# Battery.net
KiCad netlist of a schematic drawn in Altium Designer
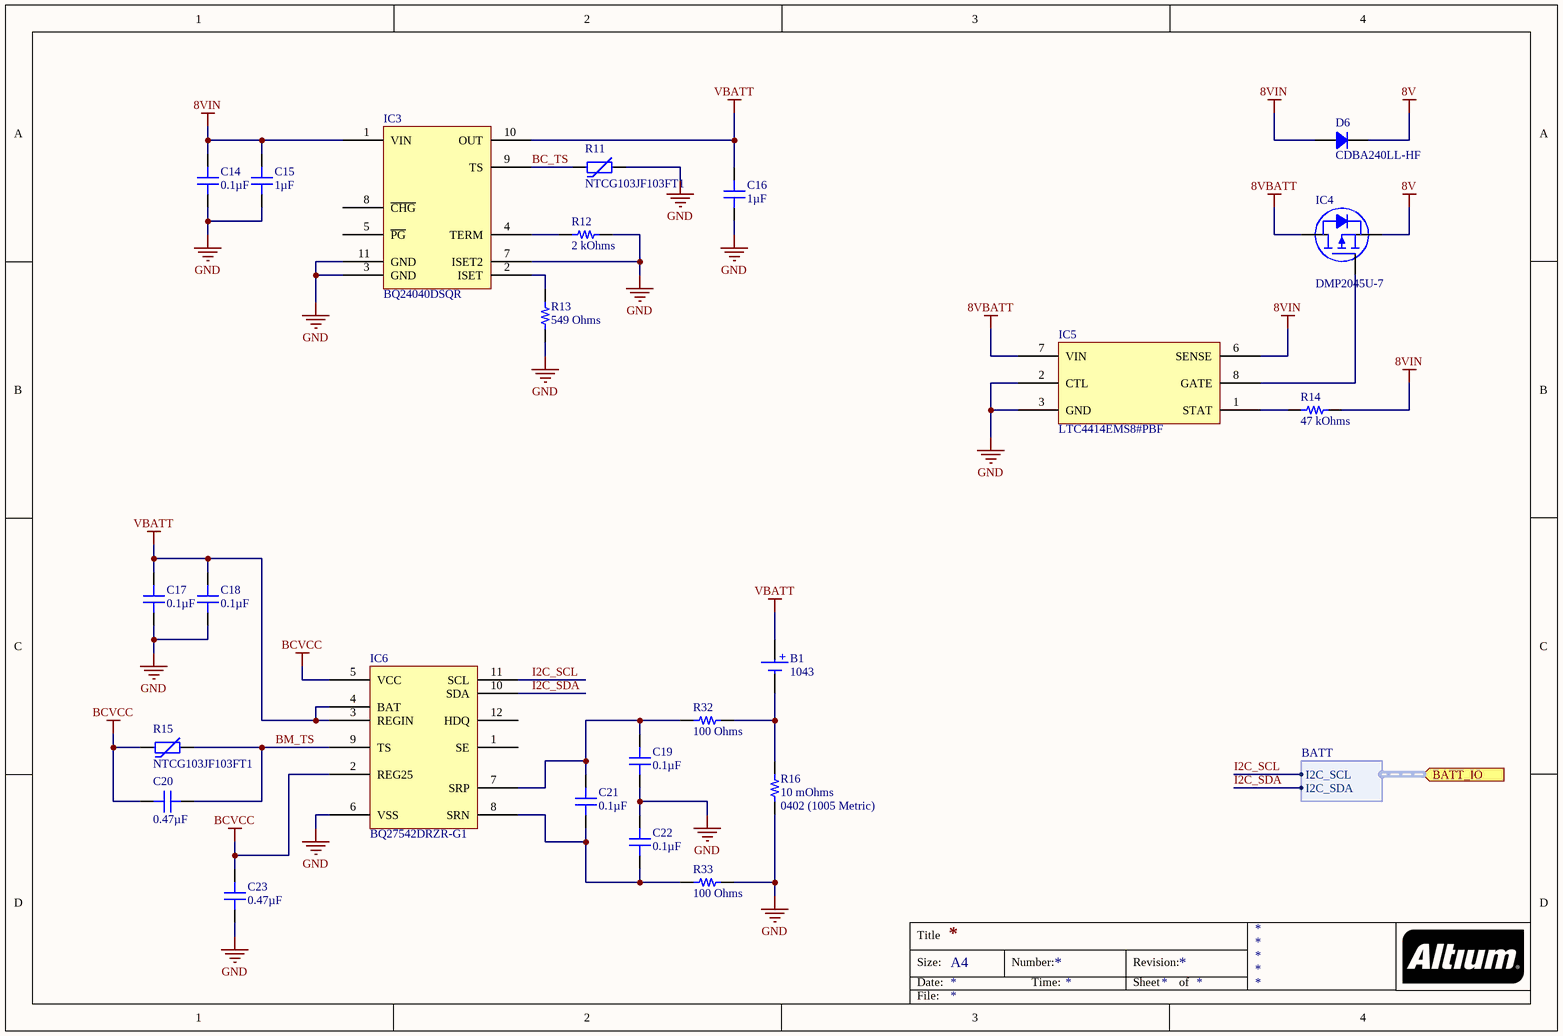
[diagram p0: Battery.SchDoc]

(export (version "E")
  (design (tool "Eeschema 10.0.6"))
  (components
    (comp (ref "B1")
      (value "1043")
      (footprint "KEYSTONE 1043")
      (description "BATTERY HOLDER 18650 PC PIN")
      (fields (field (name "MANUFACTURER") "Keystone Electronics"))
      (libsource (lib "Celestial Altium Library - altium_library") (part "Keystone 1043"))
    )
    (comp (ref "C14")
      (value "0.1µF")
      (footprint "CAP 0201_0603")
      (description "CAP CER 0.1UF 16V X5R 0201")
      (fields
        (field (name "PART NUMBER") "GRM033R61C104ME84D")
        (field (name "MANUFACTURER") "Murata Electronics")
      )
      (libsource (lib "Celestial Altium Library - altium_library") (part "Capacitor"))
    )
    (comp (ref "C15")
      (value "1µF")
      (footprint "CAP 0402_1005")
      (description "CAP CER 1UF 16V X5R 0402")
      (fields
        (field (name "PART NUMBER") "GRM155R61C105MA12D")
        (field (name "MANUFACTURER") "Murata Electronics")
      )
      (libsource (lib "Celestial Altium Library - altium_library") (part "Capacitor"))
    )
    (comp (ref "C16")
      (value "1µF")
      (footprint "CAP 0402_1005")
      (description "CAP CER 1UF 16V X5R 0402")
      (fields
        (field (name "PART NUMBER") "GRM155R61C105MA12D")
        (field (name "MANUFACTURER") "Murata Electronics")
      )
      (libsource (lib "Celestial Altium Library - altium_library") (part "Capacitor"))
    )
    (comp (ref "C17")
      (value "0.1µF")
      (footprint "CAP 0201_0603")
      (description "CAP CER 0.1UF 16V X5R 0201")
      (fields
        (field (name "PART NUMBER") "GRM033R61C104ME84D")
        (field (name "MANUFACTURER") "Murata Electronics")
      )
      (libsource (lib "Celestial Altium Library - altium_library") (part "Capacitor"))
    )
    (comp (ref "C18")
      (value "0.1µF")
      (footprint "CAP 0201_0603")
      (description "CAP CER 0.1UF 16V X5R 0201")
      (fields
        (field (name "PART NUMBER") "GRM033R61C104ME84D")
        (field (name "MANUFACTURER") "Murata Electronics")
      )
      (libsource (lib "Celestial Altium Library - altium_library") (part "Capacitor"))
    )
    (comp (ref "C19")
      (value "0.1µF")
      (footprint "CAP 0201_0603")
      (description "CAP CER 0.1UF 16V X5R 0201")
      (fields
        (field (name "PART NUMBER") "GRM033R61C104ME84D")
        (field (name "MANUFACTURER") "Murata Electronics")
      )
      (libsource (lib "Celestial Altium Library - altium_library") (part "Capacitor"))
    )
    (comp (ref "C20")
      (value "0.47µF")
      (footprint "CAP 0201_0603")
      (description "CAP CER 0.47UF 6.3V X5R 0201")
      (fields
        (field (name "PART NUMBER") "GRM033R60J474ME90D")
        (field (name "MANUFACTURER") "Murata Electronics")
      )
      (libsource (lib "Celestial Altium Library - altium_library") (part "Capacitor"))
    )
    (comp (ref "C21")
      (value "0.1µF")
      (footprint "CAP 0201_0603")
      (description "CAP CER 0.1UF 16V X5R 0201")
      (fields
        (field (name "PART NUMBER") "GRM033R61C104ME84D")
        (field (name "MANUFACTURER") "Murata Electronics")
      )
      (libsource (lib "Celestial Altium Library - altium_library") (part "Capacitor"))
    )
    (comp (ref "C22")
      (value "0.1µF")
      (footprint "CAP 0201_0603")
      (description "CAP CER 0.1UF 16V X5R 0201")
      (fields
        (field (name "PART NUMBER") "GRM033R61C104ME84D")
        (field (name "MANUFACTURER") "Murata Electronics")
      )
      (libsource (lib "Celestial Altium Library - altium_library") (part "Capacitor"))
    )
    (comp (ref "C23")
      (value "0.47µF")
      (footprint "CAP 0201_0603")
      (description "CAP CER 0.47UF 6.3V X5R 0201")
      (fields
        (field (name "PART NUMBER") "GRM033R60J474ME90D")
        (field (name "MANUFACTURER") "Murata Electronics")
      )
      (libsource (lib "Celestial Altium Library - altium_library") (part "Capacitor"))
    )
    (comp (ref "D6")
      (value "CDBA240LL-HF")
      (footprint "DO214AC SMA")
      (description "DIODE SCHOTTKY 40V 2A DO214AC")
      (fields (field (name "MANUFACTURER") "Comchip Technology"))
      (libsource (lib "Celestial Altium Library - altium_library") (part "Diode"))
    )
    (comp (ref "IC3")
      (value "BQ24040DSQR")
      (footprint "TI PWSON-10 DSQ")
      (description "IC BATT CHG LI-ION 1 CELL 10SON")
      (fields (field (name "MANUFACTURER") "Texas Instruments"))
      (libsource (lib "Celestial Altium Library - altium_library") (part "TI BQ24040/45"))
    )
    (comp (ref "IC4")
      (value "DMP2045U-7")
      (footprint "DIODES SOT-23-3")
      (description "MOSFET P-CHAN 24V SOT23")
      (fields (field (name "MANUFACTURER") "Diodes Incorporated"))
      (libsource (lib "Celestial Altium Library - altium_library") (part "DIODES MOSFET P-CH SOT-23-3"))
    )
    (comp (ref "IC5")
      (value "LTC4414EMS8#PBF")
      (footprint "ANALOG MSOP-8 RM-8")
      (description "IC OR CTRLR SRC SELECT 8MSOP")
      (fields (field (name "MANUFACTURER") "Linear Technology/Analog Devices"))
      (libsource (lib "Celestial Altium Library - altium_library") (part "ANALOG LTC4414"))
    )
    (comp (ref "IC6")
      (value "BQ27542DRZR-G1")
      (footprint "TI SON-12 DRZ")
      (description "IC BATT FUEL GAUGE LI-ION 12SON")
      (fields (field (name "MANUFACTURER") "Texas Instruments"))
      (libsource (lib "Celestial Altium Library - altium_library") (part "TI BQ27542DRZR-G1"))
    )
    (comp (ref "R11")
      (value "NTCG103JF103FT1")
      (footprint "NTC 0402_1005")
      (description "THERMISTOR NTC 10KOHM 3380K 0402")
      (fields (field (name "MANUFACTURER") "TDK Corporation"))
      (libsource (lib "Celestial Altium Library - altium_library") (part "Thermistor"))
    )
    (comp (ref "R12")
      (value "2 kOhms")
      (footprint "RES 0201_0603")
      (description "RES SMD 2K OHM 1% 1/20W 0201")
      (fields
        (field (name "PART NUMBER") "ERJ-1GNF2001C")
        (field (name "MANUFACTURER") "Panasonic Electronic Components")
      )
      (libsource (lib "Celestial Altium Library - altium_library") (part "Resistor"))
    )
    (comp (ref "R13")
      (value "549 Ohms")
      (footprint "RES 0201_0603")
      (description "RES SMD 549 OHM 1% 1/20W 0201")
      (fields
        (field (name "PART NUMBER") "ERJ-1GNF5490C")
        (field (name "MANUFACTURER") "Panasonic Electronic Components")
      )
      (libsource (lib "Celestial Altium Library - altium_library") (part "Resistor"))
    )
    (comp (ref "R14")
      (value "47 kOhms")
      (footprint "RES 0201_0603")
      (description "RES SMD 47K OHM 1% 1/20W 0201")
      (fields
        (field (name "PART NUMBER") "ERJ-1GNF4702C")
        (field (name "MANUFACTURER") "Panasonic Electronic Components")
      )
      (libsource (lib "Celestial Altium Library - altium_library") (part "Resistor"))
    )
    (comp (ref "R15")
      (value "NTCG103JF103FT1")
      (footprint "NTC 0402_1005")
      (description "THERMISTOR NTC 10KOHM 3380K 0402")
      (fields (field (name "MANUFACTURER") "TDK Corporation"))
      (libsource (lib "Celestial Altium Library - altium_library") (part "Thermistor"))
    )
    (comp (ref "R16")
      (value "10 mOhms")
      (footprint "STACKPOLE CSR0402")
      (description "RES 0.01 OHM 1% 1/5W 0402")
      (fields
        (field (name "PART NUMBER") "ERJ-2LWFR010X")
        (field (name "PACKAGE / CASE") "0402 (1005 Metric)")
        (field (name "MANUFACTURER") "Panasonic Electronic Components")
      )
      (libsource (lib "Celestial Altium Library - altium_library") (part "Resistor"))
    )
    (comp (ref "R32")
      (value "100 Ohms")
      (footprint "RES 0201_0603")
      (description "RES 100 OHM 1% 1/20W 0201")
      (fields
        (field (name "PART NUMBER") "RK73H1HTTC1000F")
        (field (name "MANUFACTURER") "KOA Speer Electronics, Inc.")
      )
      (libsource (lib "Celestial Altium Library - altium_library") (part "Resistor"))
    )
    (comp (ref "R33")
      (value "100 Ohms")
      (footprint "RES 0201_0603")
      (description "RES 100 OHM 1% 1/20W 0201")
      (fields
        (field (name "PART NUMBER") "RK73H1HTTC1000F")
        (field (name "MANUFACTURER") "KOA Speer Electronics, Inc.")
      )
      (libsource (lib "Celestial Altium Library - altium_library") (part "Resistor"))
    )
  )
  (nets
    (net (code "2") (name "/BC_TS") (class "Default")
      (node (ref "IC3") (pin "9") (pinfunction "TS_9") (pintype "passive"))
      (node (ref "R11") (pin "1") (pinfunction "1_1") (pintype "passive"))
    )
    (net (code "3") (name "/BM_TS") (class "Default")
      (node (ref "C20") (pin "2") (pinfunction "2_2") (pintype "passive"))
      (node (ref "IC6") (pin "9") (pinfunction "TS_9") (pintype "passive"))
      (node (ref "R15") (pin "2") (pinfunction "2_2") (pintype "passive"))
    )
    (net (code "4") (name "/I2C_SCL") (class "Default")
      (node (ref "IC6") (pin "11") (pinfunction "SCL_11") (pintype "passive"))
    )
    (net (code "5") (name "/I2C_SDA") (class "Default")
      (node (ref "IC6") (pin "10") (pinfunction "SDA_10") (pintype "passive"))
    )
    (net (code "7") (name "8V") (class "Default")
      (node (ref "D6") (pin "2") (pinfunction "2_2") (pintype "passive"))
      (node (ref "IC4") (pin "2") (pinfunction "S_2") (pintype "passive"))
    )
    (net (code "8") (name "8VBATT") (class "Default")
      (node (ref "IC4") (pin "3") (pinfunction "D_3") (pintype "passive"))
      (node (ref "IC5") (pin "7") (pinfunction "VIN_7") (pintype "passive"))
    )
    (net (code "9") (name "8VIN") (class "Default")
      (node (ref "C14") (pin "2") (pinfunction "2_2") (pintype "passive"))
      (node (ref "C15") (pin "2") (pinfunction "2_2") (pintype "passive"))
      (node (ref "D6") (pin "1") (pinfunction "1_1") (pintype "passive"))
      (node (ref "IC3") (pin "1") (pinfunction "VIN_1") (pintype "passive"))
      (node (ref "IC5") (pin "6") (pinfunction "SENSE_6") (pintype "passive"))
      (node (ref "R14") (pin "2") (pinfunction "2_2") (pintype "passive"))
    )
    (net (code "10") (name "BCVCC") (class "Default")
      (node (ref "C20") (pin "1") (pinfunction "1_1") (pintype "passive"))
      (node (ref "C23") (pin "2") (pinfunction "2_2") (pintype "passive"))
      (node (ref "IC6") (pin "2") (pinfunction "REG25_2") (pintype "passive"))
      (node (ref "IC6") (pin "5") (pinfunction "VCC_5") (pintype "passive"))
      (node (ref "R15") (pin "1") (pinfunction "1_1") (pintype "passive"))
    )
    (net (code "11") (name "GND") (class "Default")
      (node (ref "C14") (pin "1") (pinfunction "1_1") (pintype "passive"))
      (node (ref "C15") (pin "1") (pinfunction "1_1") (pintype "passive"))
      (node (ref "C16") (pin "1") (pinfunction "1_1") (pintype "passive"))
      (node (ref "C17") (pin "1") (pinfunction "1_1") (pintype "passive"))
      (node (ref "C18") (pin "1") (pinfunction "1_1") (pintype "passive"))
      (node (ref "C19") (pin "1") (pinfunction "1_1") (pintype "passive"))
      (node (ref "C22") (pin "2") (pinfunction "2_2") (pintype "passive"))
      (node (ref "C23") (pin "1") (pinfunction "1_1") (pintype "passive"))
      (node (ref "IC3") (pin "11") (pinfunction "GND_11") (pintype "passive"))
      (node (ref "IC3") (pin "3") (pinfunction "GND_3") (pintype "passive"))
      (node (ref "IC3") (pin "7") (pinfunction "ISET2_7") (pintype "passive"))
      (node (ref "IC5") (pin "2") (pinfunction "CTL_2") (pintype "passive"))
      (node (ref "IC5") (pin "3") (pinfunction "GND_3") (pintype "passive"))
      (node (ref "IC6") (pin "6") (pinfunction "VSS_6") (pintype "passive"))
      (node (ref "R11") (pin "2") (pinfunction "2_2") (pintype "passive"))
      (node (ref "R12") (pin "2") (pinfunction "2_2") (pintype "passive"))
      (node (ref "R13") (pin "1") (pinfunction "1_1") (pintype "passive"))
      (node (ref "R16") (pin "1") (pinfunction "1_1") (pintype "passive"))
      (node (ref "R33") (pin "2") (pinfunction "2_2") (pintype "passive"))
    )
    (net (code "12") (name "Net-(B1--)") (class "Default")
      (node (ref "B1") (pin "2") (pinfunction "-_2") (pintype "passive"))
      (node (ref "R16") (pin "2") (pinfunction "2_2") (pintype "passive"))
      (node (ref "R32") (pin "2") (pinfunction "2_2") (pintype "passive"))
    )
    (net (code "13") (name "Net-(IC3-ISET)") (class "Default")
      (node (ref "IC3") (pin "2") (pinfunction "ISET_2") (pintype "passive"))
      (node (ref "R13") (pin "2") (pinfunction "2_2") (pintype "passive"))
    )
    (net (code "14") (name "Net-(IC3-TERM)") (class "Default")
      (node (ref "IC3") (pin "4") (pinfunction "TERM_4") (pintype "passive"))
      (node (ref "R12") (pin "1") (pinfunction "1_1") (pintype "passive"))
    )
    (net (code "15") (name "Net-(IC4-G)") (class "Default")
      (node (ref "IC4") (pin "1") (pinfunction "G_1") (pintype "passive"))
      (node (ref "IC5") (pin "8") (pinfunction "GATE_8") (pintype "passive"))
    )
    (net (code "16") (name "Net-(IC5-STAT)") (class "Default")
      (node (ref "IC5") (pin "1") (pinfunction "STAT_1") (pintype "passive"))
      (node (ref "R14") (pin "1") (pinfunction "1_1") (pintype "passive"))
    )
    (net (code "17") (name "Net-(IC6-SRN)") (class "Default")
      (node (ref "C21") (pin "1") (pinfunction "1_1") (pintype "passive"))
      (node (ref "C22") (pin "1") (pinfunction "1_1") (pintype "passive"))
      (node (ref "IC6") (pin "8") (pinfunction "SRN_8") (pintype "passive"))
      (node (ref "R33") (pin "1") (pinfunction "1_1") (pintype "passive"))
    )
    (net (code "18") (name "Net-(IC6-SRP)") (class "Default")
      (node (ref "C19") (pin "2") (pinfunction "2_2") (pintype "passive"))
      (node (ref "C21") (pin "2") (pinfunction "2_2") (pintype "passive"))
      (node (ref "IC6") (pin "7") (pinfunction "SRP_7") (pintype "passive"))
      (node (ref "R32") (pin "1") (pinfunction "1_1") (pintype "passive"))
    )
    (net (code "19") (name "VBATT") (class "Default")
      (node (ref "B1") (pin "1") (pinfunction "+_1") (pintype "passive"))
      (node (ref "C16") (pin "2") (pinfunction "2_2") (pintype "passive"))
      (node (ref "C17") (pin "2") (pinfunction "2_2") (pintype "passive"))
      (node (ref "C18") (pin "2") (pinfunction "2_2") (pintype "passive"))
      (node (ref "IC3") (pin "10") (pinfunction "OUT_10") (pintype "passive"))
      (node (ref "IC6") (pin "3") (pinfunction "REGIN_3") (pintype "passive"))
      (node (ref "IC6") (pin "4") (pinfunction "BAT_4") (pintype "passive"))
    )
    (net (code "20") (name "unconnected-(IC3-~{CHG}-Pad8)") (class "Default")
      (node (ref "IC3") (pin "8") (pinfunction "~{CHG}_8") (pintype "passive"))
    )
    (net (code "21") (name "unconnected-(IC3-~{PG}-Pad5)") (class "Default")
      (node (ref "IC3") (pin "5") (pinfunction "~{PG}_5") (pintype "passive"))
    )
    (net (code "22") (name "unconnected-(IC6-HDQ-Pad12)") (class "Default")
      (node (ref "IC6") (pin "12") (pinfunction "HDQ_12") (pintype "passive"))
    )
    (net (code "23") (name "unconnected-(IC6-SE-Pad1)") (class "Default")
      (node (ref "IC6") (pin "1") (pinfunction "SE_1") (pintype "passive"))
    )
  )
)
